# PowerManagement.net
KiCad netlist of a schematic drawn in Altium Designer
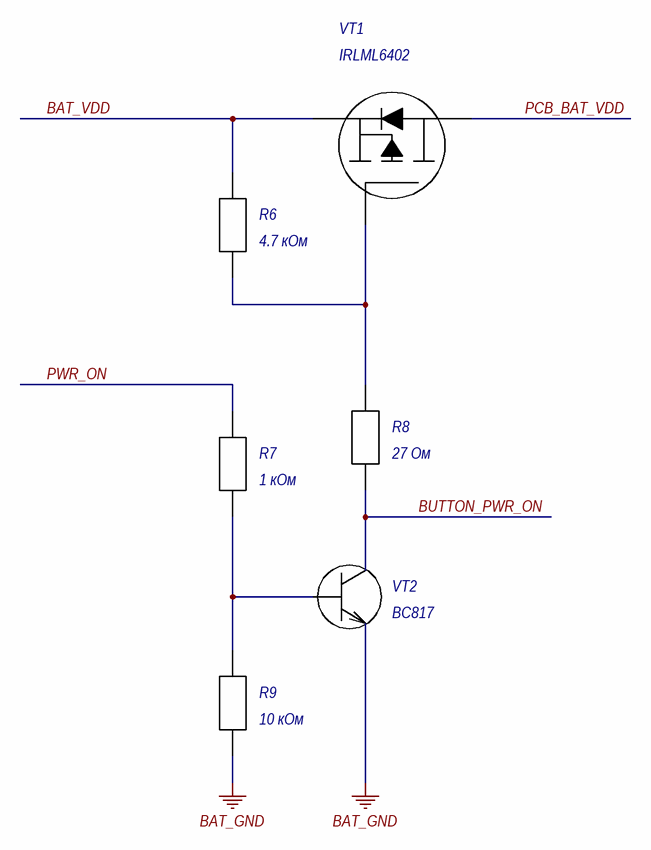
[diagram p0: PowerManagement.SchDoc]

(export (version "E")
  (design (tool "Eeschema 10.0.6"))
  (components
    (comp (ref "R6") (value "4.7 кОм") (footprint "RES 0402") (libsource (lib "my_lib") (part "RES 0402")))
    (comp (ref "R7") (value "1 кОм") (footprint "RES 0402") (libsource (lib "my_lib") (part "RES 0402")))
    (comp (ref "R8") (value "27 Ом") (footprint "RES 0402") (libsource (lib "my_lib") (part "RES 0402")))
    (comp (ref "R9") (value "10 кОм") (footprint "RES 0402") (libsource (lib "my_lib") (part "RES 0402")))
    (comp (ref "VT1") (value "IRLML6402") (footprint "SOT-23") (libsource (lib "my_lib") (part "IRLML6402")))
    (comp (ref "VT2")
      (value "BC817")
      (footprint "SOT-23")
      (description "NPN general-purpose transistor")
      (fields (field (name "MANUFACTURER") "NXP"))
      (libsource (lib "my_lib") (part "BC817"))
    )
  )
  (nets
    (net (code "1") (name "/BAT_VDD") (class "Default")
      (node (ref "R6") (pin "2") (pinfunction "2_2") (pintype "passive"))
      (node (ref "VT1") (pin "2") (pinfunction "S_2") (pintype "passive"))
    )
    (net (code "2") (name "/BUTTON_PWR_ON") (class "Default")
      (node (ref "R8") (pin "1") (pinfunction "1_1") (pintype "passive"))
      (node (ref "VT2") (pin "3") (pinfunction "C_3") (pintype "passive"))
    )
    (net (code "3") (name "/PCB_BAT_VDD") (class "Default")
      (node (ref "VT1") (pin "3") (pinfunction "D_3") (pintype "passive"))
    )
    (net (code "4") (name "/PWR_ON") (class "Default")
      (node (ref "R7") (pin "2") (pinfunction "2_2") (pintype "passive"))
    )
    (net (code "5") (name "BAT_GND") (class "Default")
      (node (ref "R9") (pin "1") (pinfunction "1_1") (pintype "passive"))
      (node (ref "VT2") (pin "2") (pinfunction "E_2") (pintype "passive"))
    )
    (net (code "6") (name "Net-(VT1-G)") (class "Default")
      (node (ref "R6") (pin "1") (pinfunction "1_1") (pintype "passive"))
      (node (ref "R8") (pin "2") (pinfunction "2_2") (pintype "passive"))
      (node (ref "VT1") (pin "1") (pinfunction "G_1") (pintype "passive"))
    )
    (net (code "7") (name "Net-(VT2-B)") (class "Default")
      (node (ref "R7") (pin "1") (pinfunction "1_1") (pintype "passive"))
      (node (ref "R9") (pin "2") (pinfunction "2_2") (pintype "passive"))
      (node (ref "VT2") (pin "1") (pinfunction "B_1") (pintype "passive"))
    )
  )
)
